# 09-USB.net
KiCad netlist of a schematic drawn in Altium Designer
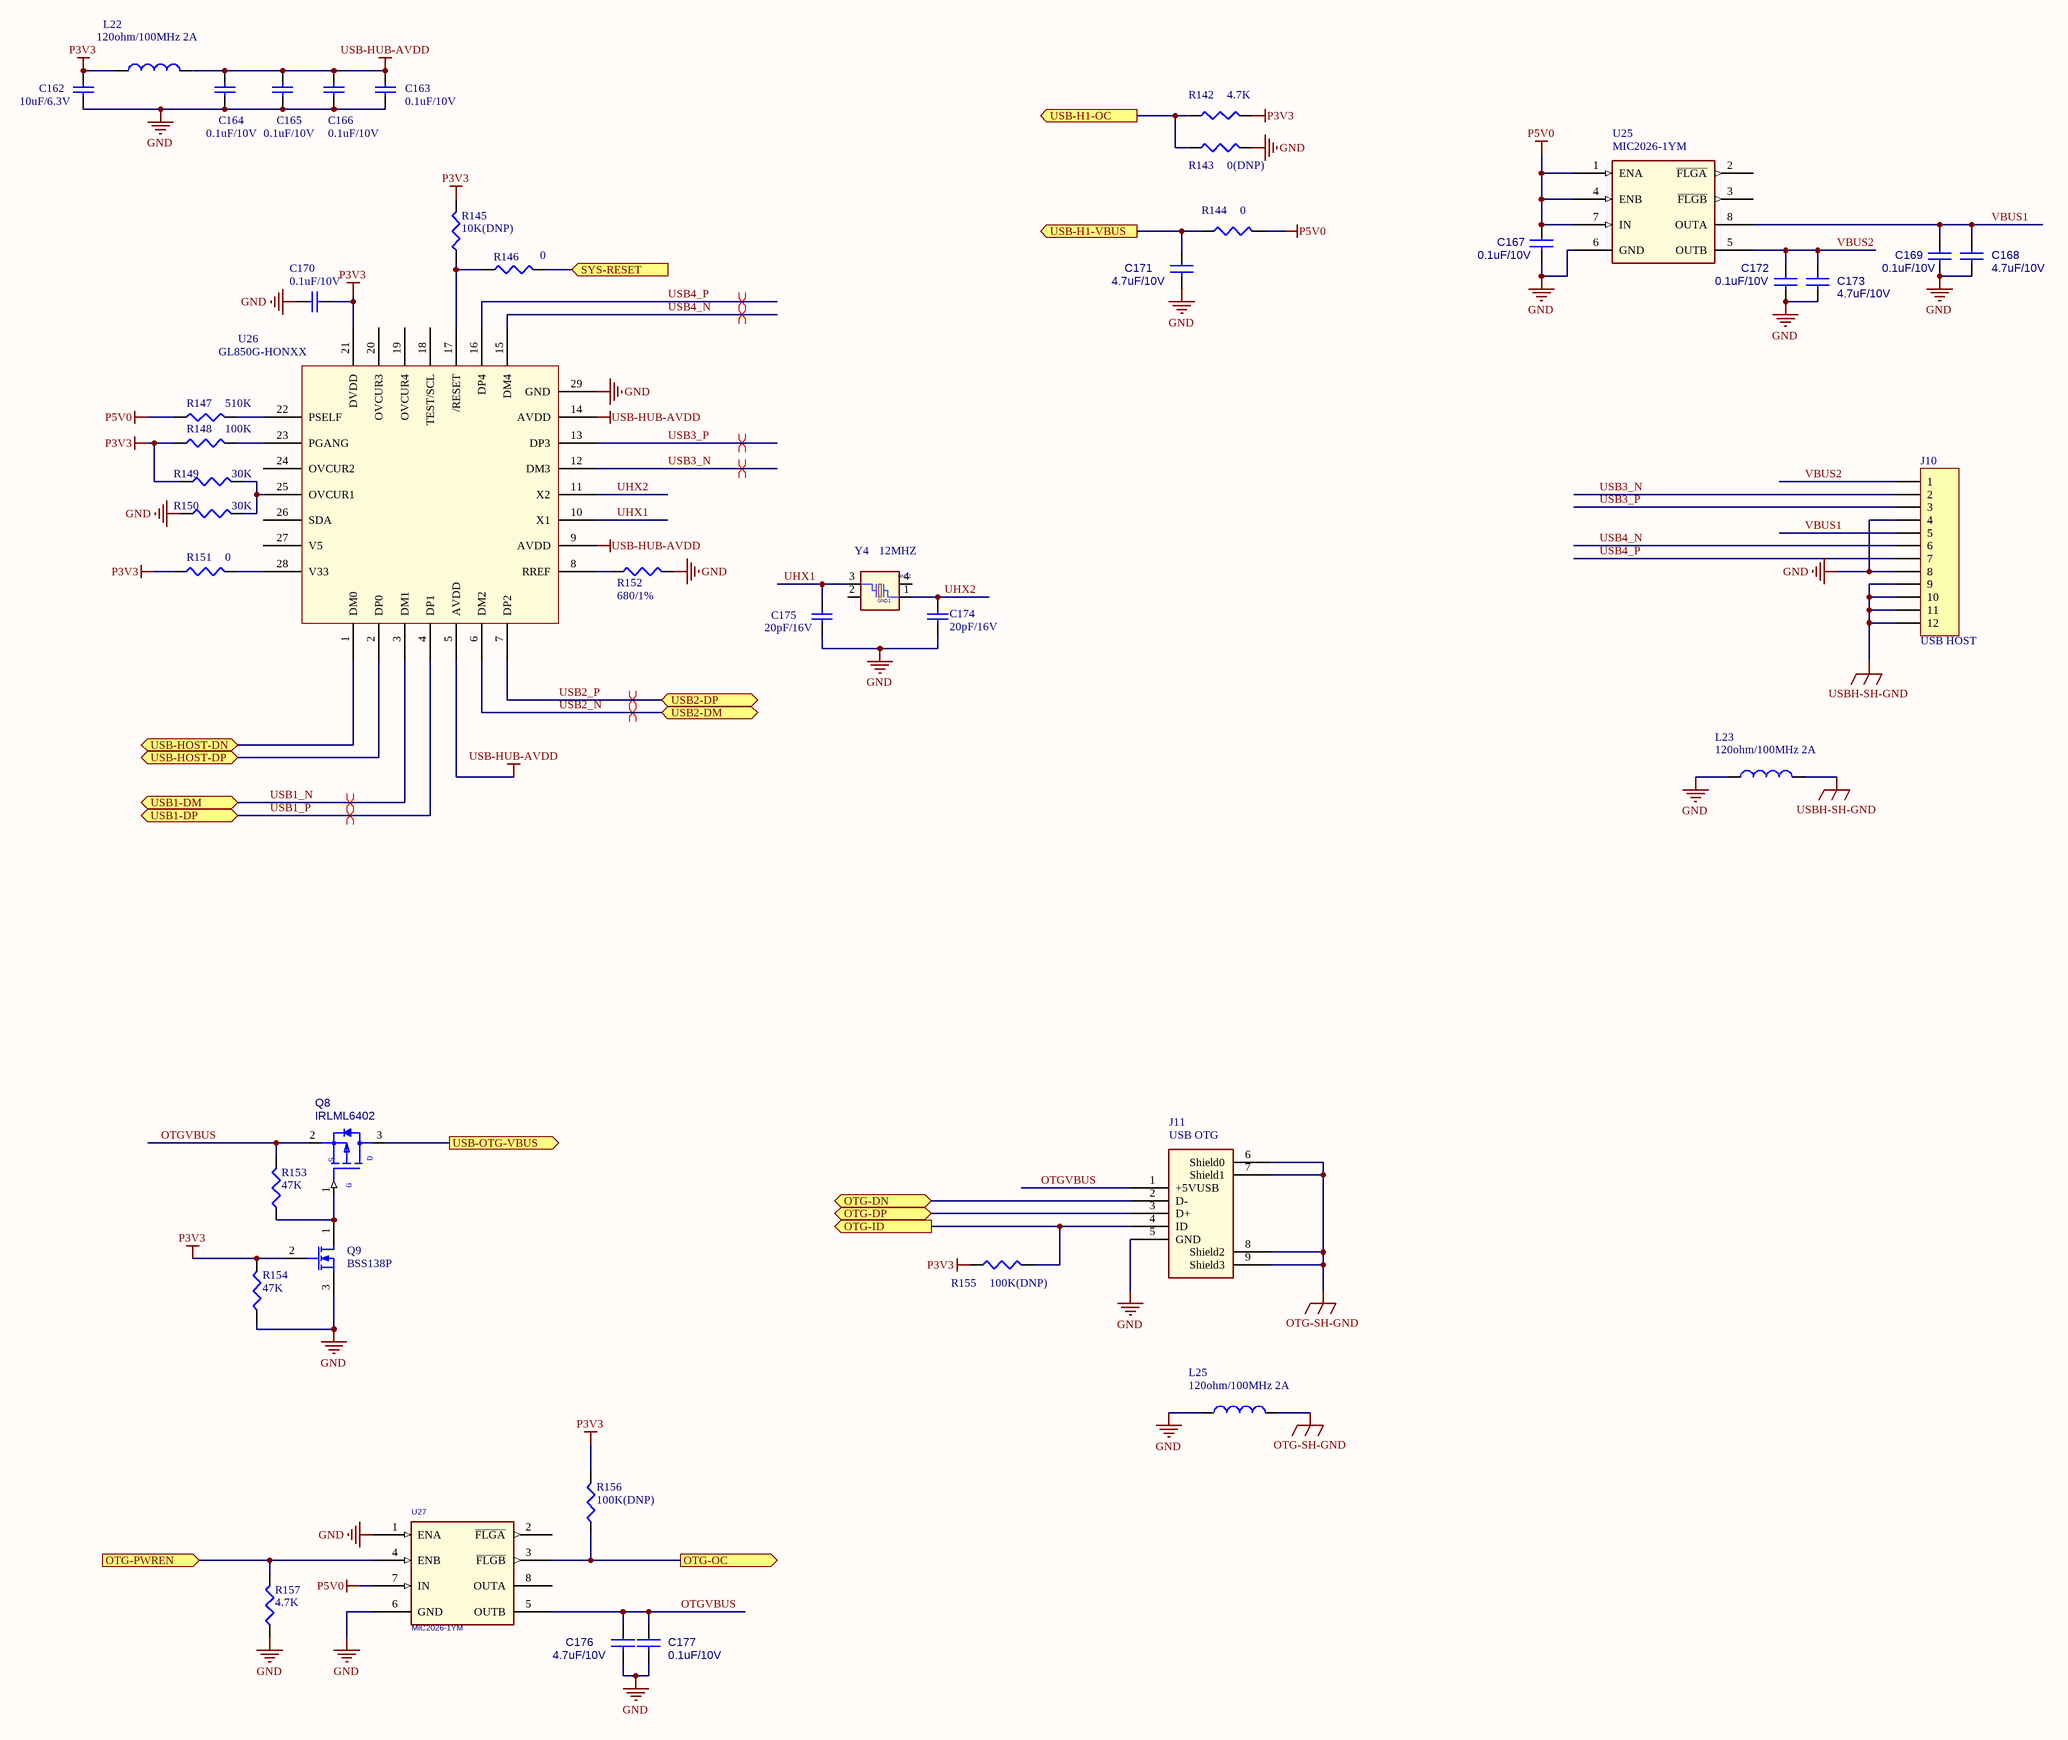
[diagram p0: 09-USB.SchDoc]

(export (version "E")
  (design (tool "Eeschema 10.0.6"))
  (components
    (comp (ref "C162")
      (value "10uF/6.3V")
      (footprint "0805")
      (description "Capacitor")
      (fields (field (name "PUBLISHER") "Altium Limited"))
      (libsource (lib "Miscellaneous Devices") (part "Cap"))
    )
    (comp (ref "C163")
      (value "0.1uF/10V")
      (footprint "0402")
      (description "Capacitor")
      (fields (field (name "PUBLISHER") "Altium Limited"))
      (libsource (lib "Miscellaneous Devices") (part "Cap"))
    )
    (comp (ref "C164")
      (value "0.1uF/10V")
      (footprint "0402")
      (description "Capacitor")
      (fields (field (name "PUBLISHER") "Altium Limited"))
      (libsource (lib "Miscellaneous Devices") (part "Cap"))
    )
    (comp (ref "C165")
      (value "0.1uF/10V")
      (footprint "0402")
      (description "Capacitor")
      (fields (field (name "PUBLISHER") "Altium Limited"))
      (libsource (lib "Miscellaneous Devices") (part "Cap"))
    )
    (comp (ref "C166")
      (value "0.1uF/10V")
      (footprint "0402")
      (description "Capacitor")
      (fields (field (name "PUBLISHER") "Altium Limited"))
      (libsource (lib "Miscellaneous Devices") (part "Cap"))
    )
    (comp (ref "C167") (value "0.1uF/10V") (libsource (lib "*") (part "CAP_Dup1")))
    (comp (ref "C168") (value "4.7uF/10V") (libsource (lib "*") (part "CAP_Dup1")))
    (comp (ref "C169") (value "0.1uF/10V") (libsource (lib "*") (part "CAP_Dup1")))
    (comp (ref "C170")
      (value "0.1uF/10V")
      (footprint "0402")
      (description "Capacitor")
      (fields (field (name "PUBLISHER") "Altium Limited"))
      (libsource (lib "Miscellaneous Devices") (part "Cap"))
    )
    (comp (ref "C171") (value "4.7uF/10V") (libsource (lib "*") (part "CAP_Dup1")))
    (comp (ref "C172") (value "0.1uF/10V") (libsource (lib "*") (part "CAP_Dup1")))
    (comp (ref "C173") (value "4.7uF/10V") (libsource (lib "*") (part "CAP_Dup1")))
    (comp (ref "C174")
      (value "20pF/16V")
      (footprint "0402")
      (description "Capacitor")
      (fields (field (name "PUBLISHER") "Altium Limited"))
      (libsource (lib "Miscellaneous Devices") (part "Cap"))
    )
    (comp (ref "C175")
      (value "20pF/16V")
      (footprint "0402")
      (description "Capacitor")
      (fields (field (name "PUBLISHER") "Altium Limited"))
      (libsource (lib "Miscellaneous Devices") (part "Cap"))
    )
    (comp (ref "C176") (value "4.7uF/10V") (libsource (lib "*") (part "CAP_Dup1")))
    (comp (ref "C177") (value "0.1uF/10V") (libsource (lib "*") (part "CAP_Dup1")))
    (comp (ref "J10")
      (value "USB HOST")
      (footprint "USB-HOST-2")
      (description "Header, 12-Pin")
      (fields (field (name "PUBLISHER") "Altium Limited"))
      (libsource (lib "Miscellaneous Connectors") (part "Header 12"))
    )
    (comp (ref "J11")
      (value "USB OTG")
      (footprint "MINIUSB-TYPEAB")
      (fields (field (name "PART NUMBER") "SP063100800"))
      (libsource (lib "*") (part "FOX_UH51543-JS7"))
    )
    (comp (ref "L22")
      (value "120ohm/100MHz 2A")
      (footprint "0603")
      (description "Inductor")
      (fields (field (name "PUBLISHER") "Altium Limited"))
      (libsource (lib "Miscellaneous Devices") (part "Inductor"))
    )
    (comp (ref "L23")
      (value "120ohm/100MHz 2A")
      (footprint "0603")
      (description "Inductor")
      (fields (field (name "PUBLISHER") "Altium Limited"))
      (libsource (lib "Miscellaneous Devices") (part "Inductor"))
    )
    (comp (ref "L25")
      (value "120ohm/100MHz 2A")
      (footprint "0603")
      (description "Inductor")
      (fields (field (name "PUBLISHER") "Altium Limited"))
      (libsource (lib "Miscellaneous Devices") (part "Inductor"))
    )
    (comp (ref "Q8")
      (value "IRLML6402")
      (footprint "MOSFET")
      (fields (field (name "PART NUMBER") "SB934010010"))
      (libsource (lib "*") (part "AO3401L_SOT23-3_0"))
    )
    (comp (ref "Q9")
      (value "BSS138P")
      (footprint "NPN")
      (description "N-Channel MOSFET")
      (fields (field (name "PUBLISHER") "Altium Limited"))
      (libsource (lib "Miscellaneous Devices") (part "MOSFET-N"))
    )
    (comp (ref "R142") (value "4.7K") (footprint "0402") (libsource (lib "*") (part "CR16-1003FM")))
    (comp (ref "R143") (value "0(DNP)") (footprint "0402") (libsource (lib "*") (part "CR16-1003FM")))
    (comp (ref "R144") (value "0") (footprint "0603") (libsource (lib "*") (part "CR16-1003FM")))
    (comp (ref "R145") (value "10K(DNP)") (footprint "0402") (libsource (lib "*") (part "CR16-1003FM")))
    (comp (ref "R146") (value "0") (footprint "0402") (libsource (lib "*") (part "CR16-1003FM")))
    (comp (ref "R147") (value "510K") (footprint "0402") (libsource (lib "*") (part "CR16-1003FM")))
    (comp (ref "R148") (value "100K") (footprint "0402") (libsource (lib "*") (part "CR16-1003FM")))
    (comp (ref "R149") (value "30K") (footprint "0402") (libsource (lib "*") (part "CR16-1003FM")))
    (comp (ref "R150") (value "30K") (footprint "0402") (libsource (lib "*") (part "CR16-1003FM")))
    (comp (ref "R151") (value "0") (footprint "0402") (libsource (lib "*") (part "CR16-1003FM")))
    (comp (ref "R152") (value "680/1%") (footprint "0402") (libsource (lib "*") (part "CR16-1003FM")))
    (comp (ref "R153") (value "47K") (footprint "0402") (libsource (lib "*") (part "CR16-1003FM")))
    (comp (ref "R154") (value "47K") (footprint "0402") (libsource (lib "*") (part "CR16-1003FM")))
    (comp (ref "R155") (value "100K(DNP)") (footprint "0402") (libsource (lib "*") (part "CR16-1003FM")))
    (comp (ref "R156") (value "100K(DNP)") (footprint "0402") (libsource (lib "*") (part "CR16-1003FM")))
    (comp (ref "R157") (value "4.7K") (footprint "0402") (libsource (lib "*") (part "CR16-1003FM")))
    (comp (ref "U25")
      (value "MIC2026-1YM")
      (footprint "SO8")
      (description "IC LIN SW PWR ACTIVE HIGH DUAL 2.7V-5.5V 0.5A SOIC8")
      (libsource (lib "*") (part "MIC2526_8P"))
    )
    (comp (ref "U26") (value "GL850G-HONXX") (libsource (lib "Schlib") (part "GL850G-HONXX")))
    (comp (ref "U27")
      (value "MIC2026-1YM")
      (footprint "SO8")
      (description "IC LIN SW PWR ACTIVE HIGH DUAL 2.7V-5.5V 0.5A SOIC8")
      (libsource (lib "*") (part "MIC2526_8P"))
    )
    (comp (ref "Y4")
      (value "12MHZ")
      (footprint "XTAL4_SX_3225")
      (description "XTAL 28.63636MHZ 10PF RSN -- SMT")
      (libsource (lib "*") (part "CRYSTAL_JXS63"))
    )
  )
  (nets
    (net (code "1") (name "/OTG-DN") (class "Default")
      (node (ref "J11") (pin "2") (pinfunction "D-_2") (pintype "passive"))
    )
    (net (code "2") (name "/OTG-DP") (class "Default")
      (node (ref "J11") (pin "3") (pinfunction "D+_3") (pintype "passive"))
    )
    (net (code "3") (name "/OTG-ID") (class "Default")
      (node (ref "J11") (pin "4") (pinfunction "ID_4") (pintype "passive"))
      (node (ref "R155") (pin "2") (pinfunction "2_2") (pintype "passive"))
    )
    (net (code "4") (name "/OTG-OC") (class "Default")
      (node (ref "R156") (pin "1") (pinfunction "1_1") (pintype "passive"))
      (node (ref "U27") (pin "3") (pinfunction "~{FLGB}_3") (pintype "output"))
    )
    (net (code "5") (name "/OTG-PWREN") (class "Default")
      (node (ref "R157") (pin "2") (pinfunction "2_2") (pintype "passive"))
      (node (ref "U27") (pin "4") (pinfunction "ENB_4") (pintype "input"))
    )
    (net (code "6") (name "/OTGVBUS") (class "Default")
      (node (ref "C176") (pin "1") (pinfunction "1_1") (pintype "passive"))
      (node (ref "C177") (pin "1") (pinfunction "1_1") (pintype "passive"))
      (node (ref "J11") (pin "1") (pinfunction "+5VUSB_1") (pintype "passive"))
      (node (ref "Q8") (pin "2") (pinfunction "S_2") (pintype "passive"))
      (node (ref "R153") (pin "2") (pinfunction "2_2") (pintype "passive"))
      (node (ref "U27") (pin "5") (pinfunction "OUTB_5") (pintype "power_in"))
    )
    (net (code "7") (name "/SYS-RESET") (class "Default")
      (node (ref "R146") (pin "2") (pinfunction "2_2") (pintype "passive"))
    )
    (net (code "8") (name "/UHX1") (class "Default")
      (node (ref "C175") (pin "2") (pinfunction "2_2") (pintype "passive"))
      (node (ref "U26") (pin "10") (pinfunction "X1_10") (pintype "passive"))
      (node (ref "Y4") (pin "3") (pinfunction "3_3") (pintype "passive"))
    )
    (net (code "9") (name "/UHX2") (class "Default")
      (node (ref "C174") (pin "2") (pinfunction "2_2") (pintype "passive"))
      (node (ref "U26") (pin "11") (pinfunction "X2_11") (pintype "passive"))
      (node (ref "Y4") (pin "1") (pinfunction "1_1") (pintype "passive"))
    )
    (net (code "10") (name "/USB-H1-OC") (class "Default")
      (node (ref "R142") (pin "1") (pinfunction "1_1") (pintype "passive"))
      (node (ref "R143") (pin "1") (pinfunction "1_1") (pintype "passive"))
    )
    (net (code "11") (name "/USB-H1-VBUS") (class "Default")
      (node (ref "C171") (pin "1") (pinfunction "1_1") (pintype "passive"))
      (node (ref "R144") (pin "1") (pinfunction "1_1") (pintype "passive"))
    )
    (net (code "12") (name "/USB-HOST-DN") (class "Default")
      (node (ref "U26") (pin "1") (pinfunction "DM0_1") (pintype "passive"))
    )
    (net (code "13") (name "/USB-HOST-DP") (class "Default")
      (node (ref "U26") (pin "2") (pinfunction "DP0_2") (pintype "passive"))
    )
    (net (code "14") (name "/USB-OTG-VBUS") (class "Default")
      (node (ref "Q8") (pin "3") (pinfunction "D_3") (pintype "passive"))
    )
    (net (code "15") (name "/USB1_N") (class "Default")
      (node (ref "U26") (pin "3") (pinfunction "DM1_3") (pintype "passive"))
    )
    (net (code "16") (name "/USB1_P") (class "Default")
      (node (ref "U26") (pin "4") (pinfunction "DP1_4") (pintype "passive"))
    )
    (net (code "17") (name "/USB2_N") (class "Default")
      (node (ref "U26") (pin "6") (pinfunction "DM2_6") (pintype "passive"))
    )
    (net (code "18") (name "/USB2_P") (class "Default")
      (node (ref "U26") (pin "7") (pinfunction "DP2_7") (pintype "passive"))
    )
    (net (code "19") (name "/USB3_N") (class "Default")
      (node (ref "J10") (pin "2") (pinfunction "2_2") (pintype "passive"))
      (node (ref "U26") (pin "12") (pinfunction "DM3_12") (pintype "passive"))
    )
    (net (code "20") (name "/USB3_P") (class "Default")
      (node (ref "J10") (pin "3") (pinfunction "3_3") (pintype "passive"))
      (node (ref "U26") (pin "13") (pinfunction "DP3_13") (pintype "passive"))
    )
    (net (code "21") (name "/USB4_N") (class "Default")
      (node (ref "J10") (pin "6") (pinfunction "6_6") (pintype "passive"))
      (node (ref "U26") (pin "15") (pinfunction "DM4_15") (pintype "passive"))
    )
    (net (code "22") (name "/USB4_P") (class "Default")
      (node (ref "J10") (pin "7") (pinfunction "7_7") (pintype "passive"))
      (node (ref "U26") (pin "16") (pinfunction "DP4_16") (pintype "passive"))
    )
    (net (code "23") (name "/VBUS1") (class "Default")
      (node (ref "C168") (pin "1") (pinfunction "1_1") (pintype "passive"))
      (node (ref "C169") (pin "1") (pinfunction "1_1") (pintype "passive"))
      (node (ref "J10") (pin "5") (pinfunction "5_5") (pintype "passive"))
      (node (ref "U25") (pin "8") (pinfunction "OUTA_8") (pintype "power_in"))
    )
    (net (code "24") (name "/VBUS2") (class "Default")
      (node (ref "C172") (pin "1") (pinfunction "1_1") (pintype "passive"))
      (node (ref "C173") (pin "1") (pinfunction "1_1") (pintype "passive"))
      (node (ref "J10") (pin "1") (pinfunction "1_1") (pintype "passive"))
      (node (ref "U25") (pin "5") (pinfunction "OUTB_5") (pintype "power_in"))
    )
    (net (code "25") (name "GND") (class "Default")
      (node (ref "C162") (pin "1") (pinfunction "1_1") (pintype "passive"))
      (node (ref "C163") (pin "1") (pinfunction "1_1") (pintype "passive"))
      (node (ref "C164") (pin "1") (pinfunction "1_1") (pintype "passive"))
      (node (ref "C165") (pin "1") (pinfunction "1_1") (pintype "passive"))
      (node (ref "C166") (pin "1") (pinfunction "1_1") (pintype "passive"))
      (node (ref "C167") (pin "2") (pinfunction "2_2") (pintype "passive"))
      (node (ref "C168") (pin "2") (pinfunction "2_2") (pintype "passive"))
      (node (ref "C169") (pin "2") (pinfunction "2_2") (pintype "passive"))
      (node (ref "C170") (pin "2") (pinfunction "2_2") (pintype "passive"))
      (node (ref "C171") (pin "2") (pinfunction "2_2") (pintype "passive"))
      (node (ref "C172") (pin "2") (pinfunction "2_2") (pintype "passive"))
      (node (ref "C173") (pin "2") (pinfunction "2_2") (pintype "passive"))
      (node (ref "C174") (pin "1") (pinfunction "1_1") (pintype "passive"))
      (node (ref "C175") (pin "1") (pinfunction "1_1") (pintype "passive"))
      (node (ref "C176") (pin "2") (pinfunction "2_2") (pintype "passive"))
      (node (ref "C177") (pin "2") (pinfunction "2_2") (pintype "passive"))
      (node (ref "J10") (pin "4") (pinfunction "4_4") (pintype "passive"))
      (node (ref "J10") (pin "8") (pinfunction "8_8") (pintype "passive"))
      (node (ref "J11") (pin "5") (pinfunction "GND_5") (pintype "passive"))
      (node (ref "L23") (pin "1") (pinfunction "1_1") (pintype "passive"))
      (node (ref "L25") (pin "1") (pinfunction "1_1") (pintype "passive"))
      (node (ref "Q9") (pin "3") (pinfunction "S_3") (pintype "passive"))
      (node (ref "R143") (pin "2") (pinfunction "2_2") (pintype "passive"))
      (node (ref "R150") (pin "1") (pinfunction "1_1") (pintype "passive"))
      (node (ref "R152") (pin "2") (pinfunction "2_2") (pintype "passive"))
      (node (ref "R154") (pin "1") (pinfunction "1_1") (pintype "passive"))
      (node (ref "R157") (pin "1") (pinfunction "1_1") (pintype "passive"))
      (node (ref "U25") (pin "6") (pinfunction "GND_6") (pintype "power_in"))
      (node (ref "U26") (pin "29") (pinfunction "GND_29") (pintype "passive"))
      (node (ref "U27") (pin "1") (pinfunction "ENA_1") (pintype "input"))
      (node (ref "U27") (pin "6") (pinfunction "GND_6") (pintype "power_in"))
    )
    (net (code "26") (name "Net-(Q8-G)") (class "Default")
      (node (ref "Q8") (pin "1") (pinfunction "G_1") (pintype "input"))
      (node (ref "Q9") (pin "1") (pinfunction "D_1") (pintype "passive"))
      (node (ref "R153") (pin "1") (pinfunction "1_1") (pintype "passive"))
    )
    (net (code "27") (name "Net-(U26-OVCUR1)") (class "Default")
      (node (ref "R149") (pin "2") (pinfunction "2_2") (pintype "passive"))
      (node (ref "R150") (pin "2") (pinfunction "2_2") (pintype "passive"))
      (node (ref "U26") (pin "25") (pinfunction "OVCUR1_25") (pintype "passive"))
    )
    (net (code "28") (name "Net-(U26-PGANG)") (class "Default")
      (node (ref "R148") (pin "2") (pinfunction "2_2") (pintype "passive"))
      (node (ref "U26") (pin "23") (pinfunction "PGANG_23") (pintype "passive"))
    )
    (net (code "29") (name "Net-(U26-PSELF)") (class "Default")
      (node (ref "R147") (pin "2") (pinfunction "2_2") (pintype "passive"))
      (node (ref "U26") (pin "22") (pinfunction "PSELF_22") (pintype "passive"))
    )
    (net (code "30") (name "Net-(U26-RREF)") (class "Default")
      (node (ref "R152") (pin "1") (pinfunction "1_1") (pintype "passive"))
      (node (ref "U26") (pin "8") (pinfunction "RREF_8") (pintype "passive"))
    )
    (net (code "31") (name "Net-(U26-V33)") (class "Default")
      (node (ref "R151") (pin "2") (pinfunction "2_2") (pintype "passive"))
      (node (ref "U26") (pin "28") (pinfunction "V33_28") (pintype "passive"))
    )
    (net (code "32") (name "Net-(U26-{slash}RESET)") (class "Default")
      (node (ref "R145") (pin "1") (pinfunction "1_1") (pintype "passive"))
      (node (ref "R146") (pin "1") (pinfunction "1_1") (pintype "passive"))
      (node (ref "U26") (pin "17") (pinfunction "/RESET_17") (pintype "passive"))
    )
    (net (code "33") (name "OTG-SH-GND") (class "Default")
      (node (ref "J11") (pin "6") (pinfunction "Shield0_6") (pintype "passive"))
      (node (ref "J11") (pin "7") (pinfunction "Shield1_7") (pintype "passive"))
      (node (ref "J11") (pin "8") (pinfunction "Shield2_8") (pintype "passive"))
      (node (ref "J11") (pin "9") (pinfunction "Shield3_9") (pintype "passive"))
      (node (ref "L25") (pin "2") (pinfunction "2_2") (pintype "passive"))
    )
    (net (code "34") (name "P3V3") (class "Default")
      (node (ref "C162") (pin "2") (pinfunction "2_2") (pintype "passive"))
      (node (ref "C170") (pin "1") (pinfunction "1_1") (pintype "passive"))
      (node (ref "L22") (pin "1") (pinfunction "1_1") (pintype "passive"))
      (node (ref "Q9") (pin "2") (pinfunction "G_2") (pintype "passive"))
      (node (ref "R142") (pin "2") (pinfunction "2_2") (pintype "passive"))
      (node (ref "R145") (pin "2") (pinfunction "2_2") (pintype "passive"))
      (node (ref "R148") (pin "1") (pinfunction "1_1") (pintype "passive"))
      (node (ref "R149") (pin "1") (pinfunction "1_1") (pintype "passive"))
      (node (ref "R151") (pin "1") (pinfunction "1_1") (pintype "passive"))
      (node (ref "R154") (pin "2") (pinfunction "2_2") (pintype "passive"))
      (node (ref "R155") (pin "1") (pinfunction "1_1") (pintype "passive"))
      (node (ref "R156") (pin "2") (pinfunction "2_2") (pintype "passive"))
      (node (ref "U26") (pin "21") (pinfunction "DVDD_21") (pintype "passive"))
    )
    (net (code "35") (name "P5V0") (class "Default")
      (node (ref "C167") (pin "1") (pinfunction "1_1") (pintype "passive"))
      (node (ref "R144") (pin "2") (pinfunction "2_2") (pintype "passive"))
      (node (ref "R147") (pin "1") (pinfunction "1_1") (pintype "passive"))
      (node (ref "U25") (pin "1") (pinfunction "ENA_1") (pintype "input"))
      (node (ref "U25") (pin "4") (pinfunction "ENB_4") (pintype "input"))
      (node (ref "U25") (pin "7") (pinfunction "IN_7") (pintype "input"))
      (node (ref "U27") (pin "7") (pinfunction "IN_7") (pintype "input"))
    )
    (net (code "36") (name "USB-HUB-AVDD") (class "Default")
      (node (ref "C163") (pin "2") (pinfunction "2_2") (pintype "passive"))
      (node (ref "C164") (pin "2") (pinfunction "2_2") (pintype "passive"))
      (node (ref "C165") (pin "2") (pinfunction "2_2") (pintype "passive"))
      (node (ref "C166") (pin "2") (pinfunction "2_2") (pintype "passive"))
      (node (ref "L22") (pin "2") (pinfunction "2_2") (pintype "passive"))
      (node (ref "U26") (pin "14") (pinfunction "AVDD_14") (pintype "passive"))
      (node (ref "U26") (pin "5") (pinfunction "AVDD_5") (pintype "passive"))
      (node (ref "U26") (pin "9") (pinfunction "AVDD_9") (pintype "passive"))
    )
    (net (code "37") (name "USBH-SH-GND") (class "Default")
      (node (ref "J10") (pin "10") (pinfunction "10_10") (pintype "passive"))
      (node (ref "J10") (pin "11") (pinfunction "11_11") (pintype "passive"))
      (node (ref "J10") (pin "12") (pinfunction "12_12") (pintype "passive"))
      (node (ref "J10") (pin "9") (pinfunction "9_9") (pintype "passive"))
      (node (ref "L23") (pin "2") (pinfunction "2_2") (pintype "passive"))
    )
    (net (code "38") (name "unconnected-(U25-~{FLGA}-Pad2)") (class "Default")
      (node (ref "U25") (pin "2") (pinfunction "~{FLGA}_2") (pintype "output"))
    )
    (net (code "39") (name "unconnected-(U25-~{FLGB}-Pad3)") (class "Default")
      (node (ref "U25") (pin "3") (pinfunction "~{FLGB}_3") (pintype "output"))
    )
    (net (code "40") (name "unconnected-(U26-OVCUR2-Pad24)") (class "Default")
      (node (ref "U26") (pin "24") (pinfunction "OVCUR2_24") (pintype "passive"))
    )
    (net (code "41") (name "unconnected-(U26-OVCUR3-Pad20)") (class "Default")
      (node (ref "U26") (pin "20") (pinfunction "OVCUR3_20") (pintype "passive"))
    )
    (net (code "42") (name "unconnected-(U26-OVCUR4-Pad19)") (class "Default")
      (node (ref "U26") (pin "19") (pinfunction "OVCUR4_19") (pintype "passive"))
    )
    (net (code "43") (name "unconnected-(U26-SDA-Pad26)") (class "Default")
      (node (ref "U26") (pin "26") (pinfunction "SDA_26") (pintype "passive"))
    )
    (net (code "44") (name "unconnected-(U26-TEST{slash}SCL-Pad18)") (class "Default")
      (node (ref "U26") (pin "18") (pinfunction "TEST/SCL_18") (pintype "passive"))
    )
    (net (code "45") (name "unconnected-(U26-V5-Pad27)") (class "Default")
      (node (ref "U26") (pin "27") (pinfunction "V5_27") (pintype "passive"))
    )
    (net (code "46") (name "unconnected-(U27-OUTA-Pad8)") (class "Default")
      (node (ref "U27") (pin "8") (pinfunction "OUTA_8") (pintype "power_in"))
    )
    (net (code "47") (name "unconnected-(U27-~{FLGA}-Pad2)") (class "Default")
      (node (ref "U27") (pin "2") (pinfunction "~{FLGA}_2") (pintype "output"))
    )
    (net (code "48") (name "unconnected-(Y4-GND1-Pad2)") (class "Default")
      (node (ref "Y4") (pin "2") (pinfunction "GND1_2") (pintype "power_in"))
    )
    (net (code "49") (name "unconnected-(Y4-GND2-Pad4)") (class "Default")
      (node (ref "Y4") (pin "4") (pinfunction "GND2_4") (pintype "power_in"))
    )
  )
)
